# UOF_proto_3V1.net
KiCad netlist of a schematic drawn in EAGLE
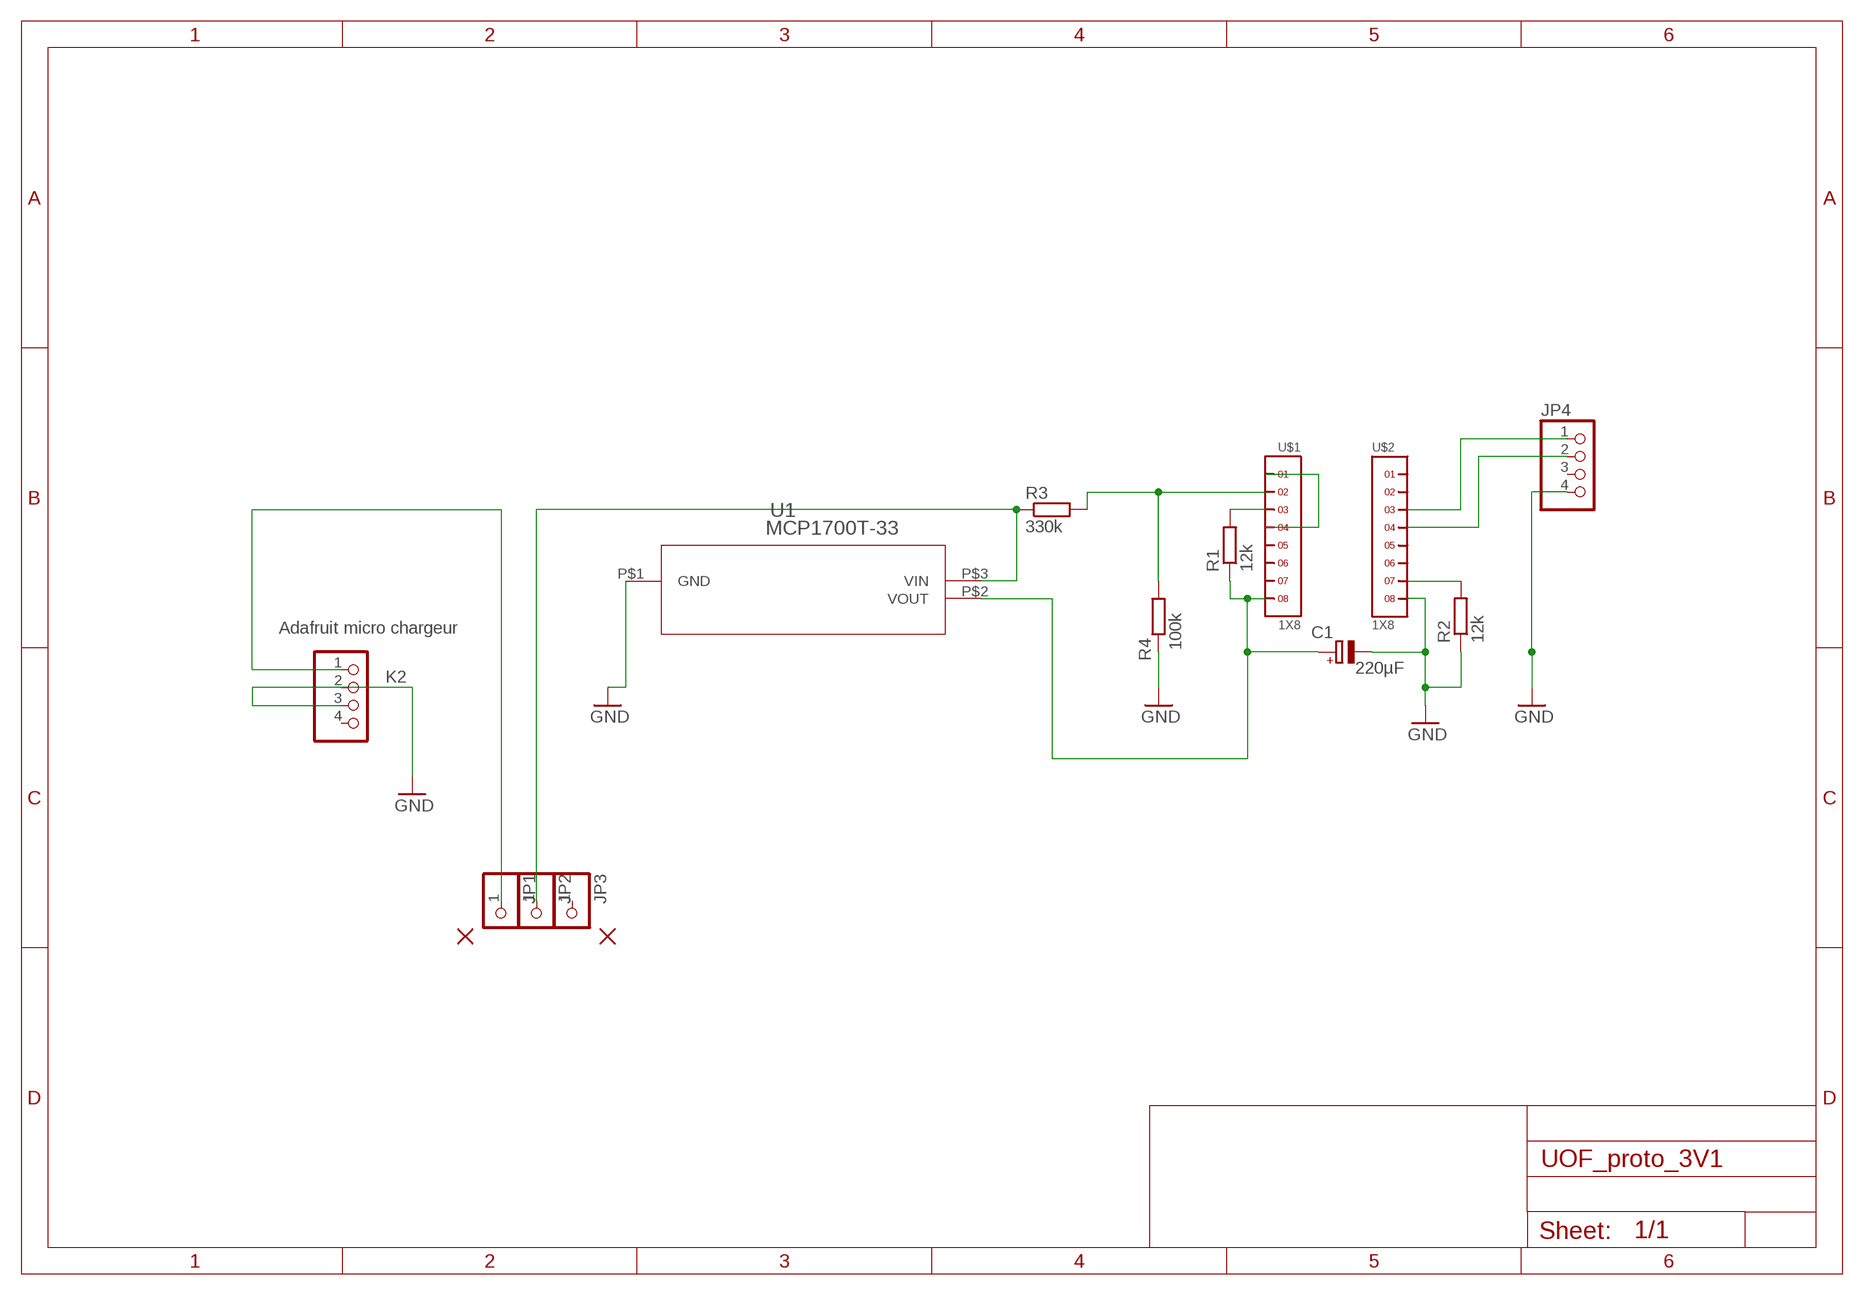
[diagram p0: schematic, sheet 1]

(export (version "E")
  (design (tool "Eeschema 10.0.6"))
  (components
    (comp (ref "C1")
      (value "220µF")
      (footprint "eagle-import:E5-10,5")
      (libsource (lib "eagle-import") (part "CPOL-EUE5-10.5"))
    )
    (comp (ref "JP1")
      (value "PINHD-1X1")
      (footprint "eagle-import:1X01")
      (libsource (lib "eagle-import") (part "PINHD-1X1"))
    )
    (comp (ref "JP2")
      (value "PINHD-1X1")
      (footprint "eagle-import:1X01")
      (libsource (lib "eagle-import") (part "PINHD-1X1"))
    )
    (comp (ref "JP3")
      (value "PINHD-1X1")
      (footprint "eagle-import:1X01")
      (libsource (lib "eagle-import") (part "PINHD-1X1"))
    )
    (comp (ref "JP4")
      (value "PINHD-1X4")
      (footprint "eagle-import:1X04")
      (libsource (lib "eagle-import") (part "PINHD-1X4"))
    )
    (comp (ref "K2")
      (value "Adafruit micro chargeur")
      (footprint "eagle-import:1X04")
      (libsource (lib "eagle-import") (part "pinhead_325_PINHD-1X4"))
    )
    (comp (ref "PAD4")
      (value "N_2,0/1,5")
      (footprint "eagle-import:2,0_1,5")
      (libsource (lib "eagle-import") (part "N_2,0/1,5"))
    )
    (comp (ref "PAD5")
      (value "N_2,0/1,5")
      (footprint "eagle-import:2,0_1,5")
      (libsource (lib "eagle-import") (part "N_2,0/1,5"))
    )
    (comp (ref "R1")
      (value "12k")
      (footprint "eagle-import:0207_10")
      (libsource (lib "eagle-import") (part "R-EU_0207/10"))
    )
    (comp (ref "R2")
      (value "12k")
      (footprint "eagle-import:0207_10")
      (libsource (lib "eagle-import") (part "R-EU_0207/10"))
    )
    (comp (ref "R3")
      (value "330k")
      (footprint "eagle-import:0207_10")
      (libsource (lib "eagle-import") (part "R-EU_0207/10"))
    )
    (comp (ref "R4")
      (value "100k")
      (footprint "eagle-import:0207_10")
      (libsource (lib "eagle-import") (part "R-EU_0207/10"))
    )
    (comp (ref "U$1")
      (value "1X8")
      (footprint "eagle-import:1X8")
      (libsource (lib "eagle-import") (part "1X8"))
    )
    (comp (ref "U$2")
      (value "1X8")
      (footprint "eagle-import:1X8")
      (libsource (lib "eagle-import") (part "1X8"))
    )
    (comp (ref "U1")
      (value "MCP1700T-33")
      (footprint "eagle-import:SOT-23")
      (libsource (lib "eagle-import") (part "MCP1700T-3302E/TTSOT-23"))
    )
  )
  (nets
    (net (code "1") (name "GND") (class "Default")
      (node (ref "C1") (pin "-") (pinfunction "-_-") (pintype "passive"))
      (node (ref "JP4") (pin "4") (pinfunction "4_4") (pintype "passive"))
      (node (ref "K2") (pin "2") (pinfunction "2_2") (pintype "passive"))
      (node (ref "K2") (pin "3") (pinfunction "3_3") (pintype "passive"))
      (node (ref "R2") (pin "1") (pinfunction "1_1") (pintype "passive"))
      (node (ref "R4") (pin "2") (pinfunction "2_2") (pintype "passive"))
      (node (ref "U$2") (pin "8") (pinfunction "8_8") (pintype "bidirectional"))
      (node (ref "U1") (pin "P$1") (pinfunction "GND_P$1") (pintype "passive"))
    )
    (net (code "2") (name "Net-(JP1-Pad1)") (class "Default")
      (node (ref "JP1") (pin "1") (pinfunction "1_1") (pintype "passive"))
      (node (ref "K2") (pin "1") (pinfunction "1_1") (pintype "passive"))
    )
    (net (code "3") (name "Net-(JP4-Pad1)") (class "Default")
      (node (ref "JP4") (pin "1") (pinfunction "1_1") (pintype "passive"))
      (node (ref "U$2") (pin "3") (pinfunction "3_3") (pintype "bidirectional"))
    )
    (net (code "4") (name "Net-(JP4-Pad2)") (class "Default")
      (node (ref "JP4") (pin "2") (pinfunction "2_2") (pintype "passive"))
      (node (ref "U$2") (pin "4") (pinfunction "4_4") (pintype "bidirectional"))
    )
    (net (code "5") (name "Net-(R1-Pad2)") (class "Default")
      (node (ref "R1") (pin "2") (pinfunction "2_2") (pintype "passive"))
      (node (ref "U$1") (pin "3") (pinfunction "3_3") (pintype "bidirectional"))
    )
    (net (code "6") (name "Net-(R2-Pad2)") (class "Default")
      (node (ref "R2") (pin "2") (pinfunction "2_2") (pintype "passive"))
      (node (ref "U$2") (pin "7") (pinfunction "7_7") (pintype "bidirectional"))
    )
    (net (code "7") (name "Net-(R3-Pad2)") (class "Default")
      (node (ref "R3") (pin "2") (pinfunction "2_2") (pintype "passive"))
      (node (ref "R4") (pin "1") (pinfunction "1_1") (pintype "passive"))
      (node (ref "U$1") (pin "2") (pinfunction "2_2") (pintype "bidirectional"))
    )
    (net (code "8") (name "Net-(U$1-Pad1)") (class "Default")
      (node (ref "U$1") (pin "1") (pinfunction "1_1") (pintype "bidirectional"))
      (node (ref "U$1") (pin "4") (pinfunction "4_4") (pintype "bidirectional"))
    )
    (net (code "9") (name "Net-(U1-VIN)") (class "Default")
      (node (ref "JP2") (pin "1") (pinfunction "1_1") (pintype "passive"))
      (node (ref "R3") (pin "1") (pinfunction "1_1") (pintype "passive"))
      (node (ref "U1") (pin "P$3") (pinfunction "VIN_P$3") (pintype "passive"))
    )
    (net (code "10") (name "Net-(U1-VOUT)") (class "Default")
      (node (ref "C1") (pin "+") (pinfunction "+_+") (pintype "passive"))
      (node (ref "R1") (pin "1") (pinfunction "1_1") (pintype "passive"))
      (node (ref "U$1") (pin "8") (pinfunction "8_8") (pintype "bidirectional"))
      (node (ref "U1") (pin "P$2") (pinfunction "VOUT_P$2") (pintype "passive"))
    )
    (net (code "11") (name "unconnected-(JP3-Pad1)") (class "Default")
      (node (ref "JP3") (pin "1") (pinfunction "1_1") (pintype "passive"))
    )
    (net (code "12") (name "unconnected-(JP4-Pad3)") (class "Default")
      (node (ref "JP4") (pin "3") (pinfunction "3_3") (pintype "passive"))
    )
    (net (code "13") (name "unconnected-(K2-Pad4)") (class "Default")
      (node (ref "K2") (pin "4") (pinfunction "4_4") (pintype "passive"))
    )
    (net (code "14") (name "unconnected-(U$1-Pad5)") (class "Default")
      (node (ref "U$1") (pin "5") (pinfunction "5_5") (pintype "bidirectional"))
    )
    (net (code "15") (name "unconnected-(U$1-Pad6)") (class "Default")
      (node (ref "U$1") (pin "6") (pinfunction "6_6") (pintype "bidirectional"))
    )
    (net (code "16") (name "unconnected-(U$1-Pad7)") (class "Default")
      (node (ref "U$1") (pin "7") (pinfunction "7_7") (pintype "bidirectional"))
    )
    (net (code "17") (name "unconnected-(U$2-Pad1)") (class "Default")
      (node (ref "U$2") (pin "1") (pinfunction "1_1") (pintype "bidirectional"))
    )
    (net (code "18") (name "unconnected-(U$2-Pad2)") (class "Default")
      (node (ref "U$2") (pin "2") (pinfunction "2_2") (pintype "bidirectional"))
    )
    (net (code "19") (name "unconnected-(U$2-Pad5)") (class "Default")
      (node (ref "U$2") (pin "5") (pinfunction "5_5") (pintype "bidirectional"))
    )
    (net (code "20") (name "unconnected-(U$2-Pad6)") (class "Default")
      (node (ref "U$2") (pin "6") (pinfunction "6_6") (pintype "bidirectional"))
    )
  )
)
